# WeatherStation.net
KiCad netlist of a schematic drawn in EAGLE
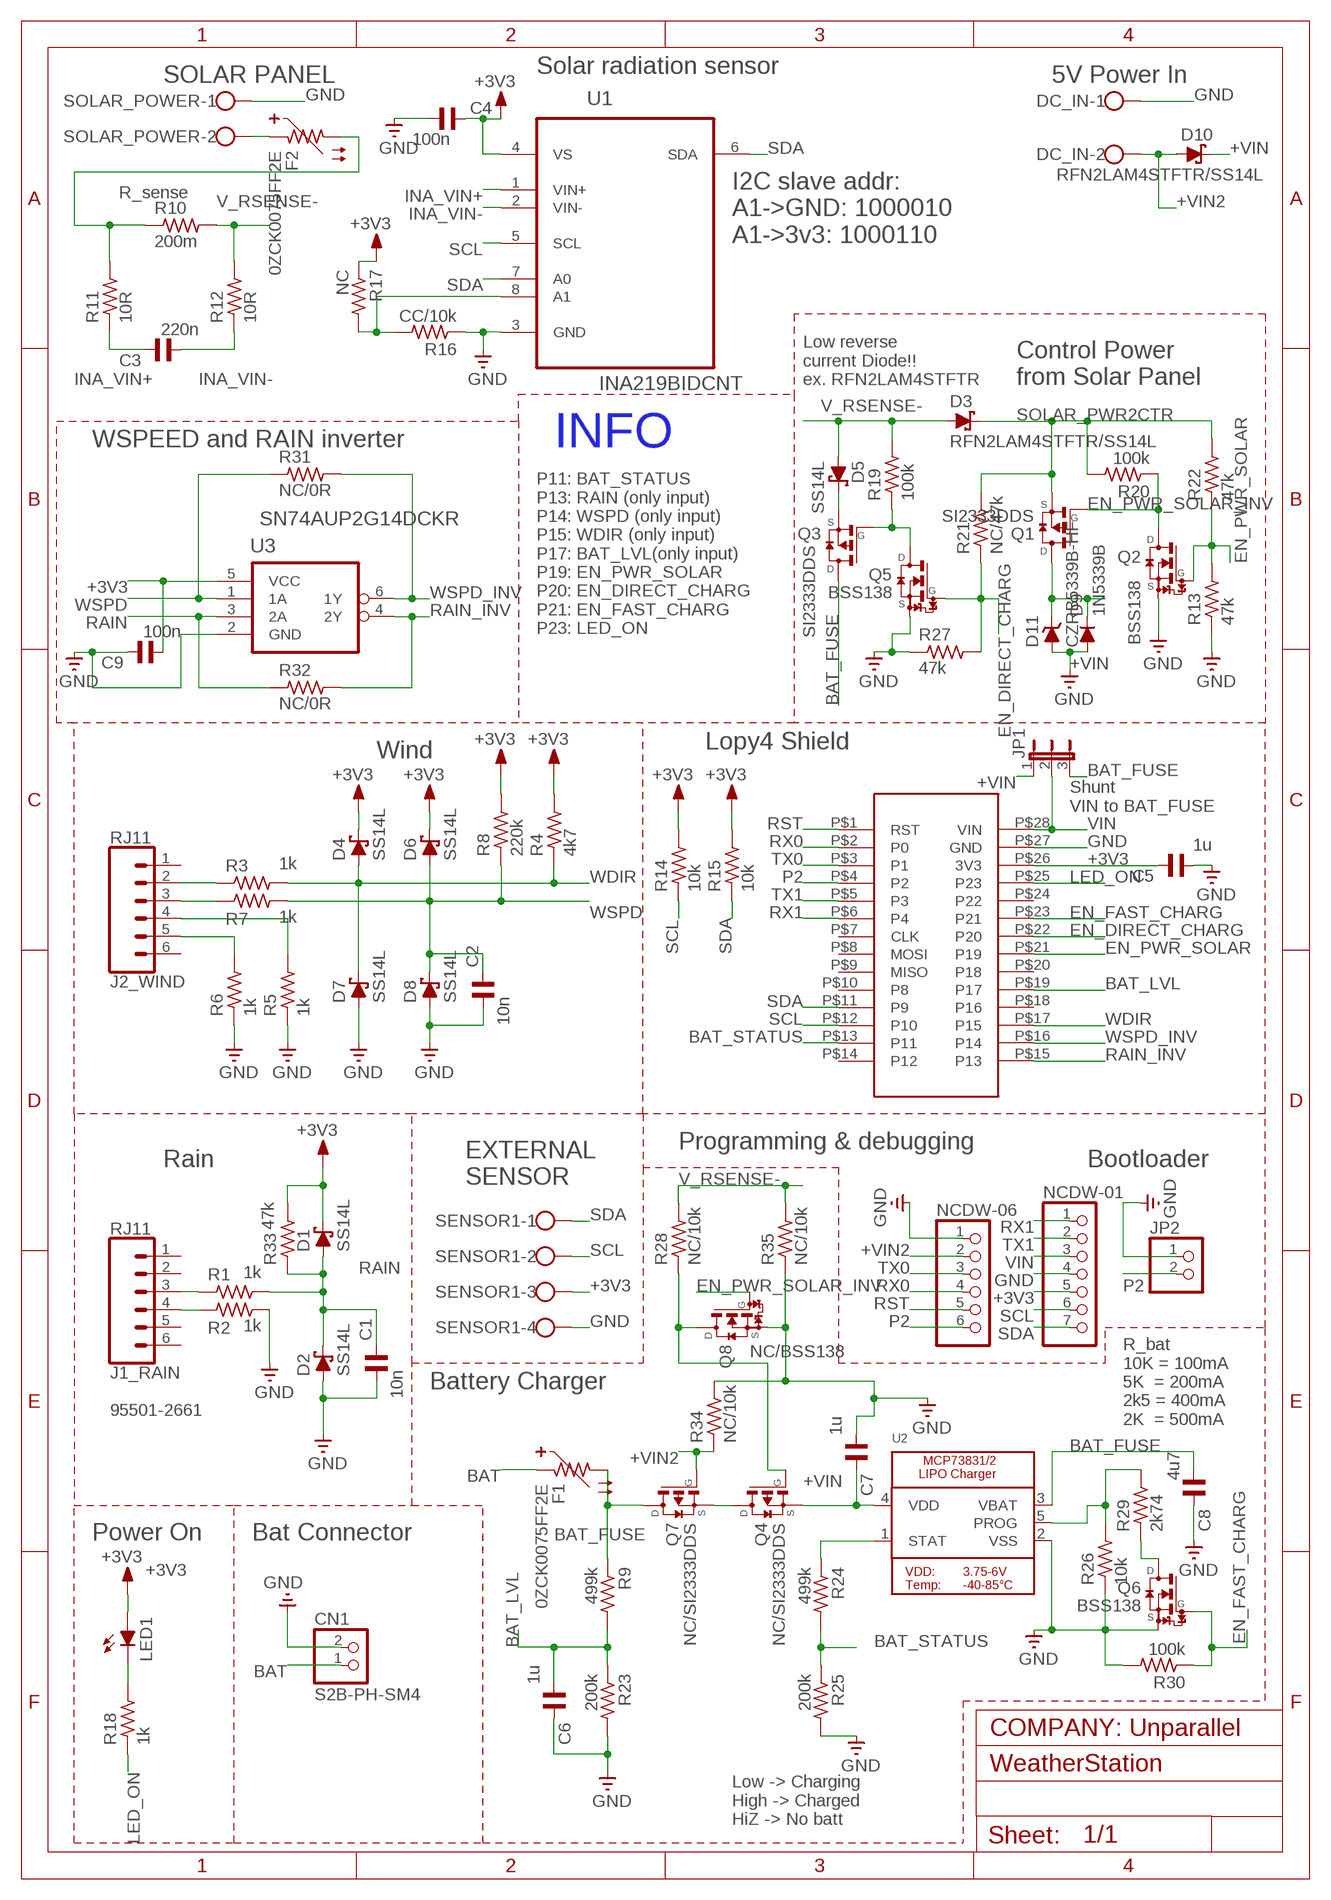
[diagram p0: schematic, sheet 1]

(export (version "E")
  (design (tool "Eeschema 10.0.6"))
  (components
    (comp (ref "C1")
      (value "10n")
      (footprint "eagle-import:C0603_C0805_PROTO_SLIM")
      (libsource (lib "eagle-import") (part "C-EUC0603/C0805_PROTO_SLIM"))
    )
    (comp (ref "C2")
      (value "10n")
      (footprint "eagle-import:C0603_C0805_PROTO_SLIM")
      (libsource (lib "eagle-import") (part "C-EUC0603/C0805_PROTO_SLIM"))
    )
    (comp (ref "C3")
      (value "220n")
      (footprint "eagle-import:C0603")
      (libsource (lib "eagle-import") (part "C-EUC0603"))
    )
    (comp (ref "C4")
      (value "100n")
      (footprint "eagle-import:C0603")
      (libsource (lib "eagle-import") (part "C-EUC0603"))
    )
    (comp (ref "C5")
      (value "1u")
      (footprint "eagle-import:C0603_C0805_PROTO_SLIM")
      (libsource (lib "eagle-import") (part "C-EUC0603/C0805_PROTO_SLIM"))
    )
    (comp (ref "C6")
      (value "1u")
      (footprint "eagle-import:C0603_C0805_PROTO_SLIM")
      (libsource (lib "eagle-import") (part "C-EUC0603/C0805_PROTO_SLIM"))
    )
    (comp (ref "C7")
      (value "1u")
      (footprint "eagle-import:C0603_C0805_PROTO_SLIM")
      (libsource (lib "eagle-import") (part "C-EUC0603/C0805_PROTO_SLIM"))
    )
    (comp (ref "C8")
      (value "4u7")
      (footprint "eagle-import:C0603_C0805_PROTO_SLIM")
      (libsource (lib "eagle-import") (part "C-EUC0603/C0805_PROTO_SLIM"))
    )
    (comp (ref "C9")
      (value "100n")
      (footprint "eagle-import:C0603")
      (libsource (lib "eagle-import") (part "C-EUC0603"))
    )
    (comp (ref "CN1")
      (value "S2B-PH-SM4")
      (footprint "eagle-import:JST-PH-2-SMT-RA")
      (libsource (lib "eagle-import") (part "JST_2PIN-SMT-RA"))
    )
    (comp (ref "D1")
      (value "SS14L")
      (footprint "eagle-import:SUB_SMA_PROTO")
      (libsource (lib "eagle-import") (part "SCHOTTKY-DIODESUB_SMA_PROTO"))
    )
    (comp (ref "D2")
      (value "SS14L")
      (footprint "eagle-import:SUB_SMA_PROTO")
      (libsource (lib "eagle-import") (part "SCHOTTKY-DIODESUB_SMA_PROTO"))
    )
    (comp (ref "D3")
      (value "RFN2LAM4STFTR/SS14L")
      (footprint "eagle-import:SMA_SOD-128_PROTO")
      (libsource (lib "eagle-import") (part "SCHOTTKY-DIODESMA_SOD-128_PROTO"))
    )
    (comp (ref "D4")
      (value "SS14L")
      (footprint "eagle-import:SUB_SMA_PROTO")
      (libsource (lib "eagle-import") (part "SCHOTTKY-DIODESUB_SMA_PROTO"))
    )
    (comp (ref "D5")
      (value "SS14L")
      (footprint "eagle-import:SUB_SMA_PROTO")
      (libsource (lib "eagle-import") (part "SCHOTTKY-DIODESUB_SMA_PROTO"))
    )
    (comp (ref "D6")
      (value "SS14L")
      (footprint "eagle-import:SUB_SMA_PROTO")
      (libsource (lib "eagle-import") (part "SCHOTTKY-DIODESUB_SMA_PROTO"))
    )
    (comp (ref "D7")
      (value "SS14L")
      (footprint "eagle-import:SUB_SMA_PROTO")
      (libsource (lib "eagle-import") (part "SCHOTTKY-DIODESUB_SMA_PROTO"))
    )
    (comp (ref "D8")
      (value "SS14L")
      (footprint "eagle-import:SUB_SMA_PROTO")
      (libsource (lib "eagle-import") (part "SCHOTTKY-DIODESUB_SMA_PROTO"))
    )
    (comp (ref "D9")
      (value "1N5339B")
      (footprint "eagle-import:DO15-12")
      (libsource (lib "eagle-import") (part "DIODE-DO15-12"))
    )
    (comp (ref "D10")
      (value "RFN2LAM4STFTR/SS14L")
      (footprint "eagle-import:SMA_SOD-128_PROTO")
      (libsource (lib "eagle-import") (part "SCHOTTKY-DIODESMA_SOD-128_PROTO"))
    )
    (comp (ref "D11")
      (value "CZRB5339B-HF")
      (footprint "eagle-import:SMB_PROTO")
      (libsource (lib "eagle-import") (part "ZENER-DIODE-PROTO"))
    )
    (comp (ref "DC_IN")
      (value "W237-102")
      (footprint "eagle-import:W237-102")
      (libsource (lib "eagle-import") (part "W237-102"))
    )
    (comp (ref "F1")
      (value "0ZCK0075FF2E")
      (footprint "eagle-import:R0603_R0805_PROTO_SLIM")
      (libsource (lib "eagle-import") (part "PTC-0603_0805_PROTO_SLIM"))
    )
    (comp (ref "F2")
      (value "0ZCK0075FF2E")
      (footprint "eagle-import:R0805")
      (libsource (lib "eagle-import") (part "PTC-0805"))
    )
    (comp (ref "J1_RAIN")
      (value "RJ11")
      (footprint "eagle-import:RJ11-6")
      (libsource (lib "eagle-import") (part "RJ11-6"))
    )
    (comp (ref "J2_WIND")
      (value "RJ11")
      (footprint "eagle-import:RJ11-6")
      (libsource (lib "eagle-import") (part "RJ11-6"))
    )
    (comp (ref "JP1")
      (value "JP2E-0805")
      (footprint "eagle-import:R0805_2")
      (libsource (lib "eagle-import") (part "JP2E-0805"))
    )
    (comp (ref "JP2")
      (value "PINHD-1X2")
      (footprint "eagle-import:1X02")
      (libsource (lib "eagle-import") (part "PINHD-1X2"))
    )
    (comp (ref "LED1")
      (value "LEDCHIP-LED0805")
      (footprint "eagle-import:CHIP-LED0805")
      (libsource (lib "eagle-import") (part "LEDCHIP-LED0805"))
    )
    (comp (ref "NCDW-01")
      (value "PINHD-1X7")
      (footprint "eagle-import:1X07")
      (libsource (lib "eagle-import") (part "PINHD-1X7"))
    )
    (comp (ref "NCDW-06")
      (value "PINHD-1X6")
      (footprint "eagle-import:1X06")
      (libsource (lib "eagle-import") (part "PINHD-1X6"))
    )
    (comp (ref "Q1")
      (value "SI2333DDS")
      (footprint "eagle-import:SOT23_PROTO_SLIM")
      (libsource (lib "eagle-import") (part "SI2333DDSPROTO_SLIM"))
    )
    (comp (ref "Q2")
      (value "BSS138")
      (footprint "eagle-import:SOT23_PROTO_SLIM")
      (libsource (lib "eagle-import") (part "NX7002AKPROTO_SLIM"))
    )
    (comp (ref "Q3")
      (value "SI2333DDS")
      (footprint "eagle-import:SOT23_PROTO_SLIM")
      (libsource (lib "eagle-import") (part "SI2333DDSPROTO_SLIM"))
    )
    (comp (ref "Q4")
      (value "NC/SI2333DDS")
      (footprint "eagle-import:SOT23_PROTO_SLIM")
      (libsource (lib "eagle-import") (part "SI2333DDSPROTO_SLIM"))
    )
    (comp (ref "Q5")
      (value "BSS138")
      (footprint "eagle-import:SOT23_PROTO_SLIM")
      (libsource (lib "eagle-import") (part "NX7002AKPROTO_SLIM"))
    )
    (comp (ref "Q6")
      (value "BSS138")
      (footprint "eagle-import:SOT23_PROTO_SLIM")
      (libsource (lib "eagle-import") (part "NX7002AKPROTO_SLIM"))
    )
    (comp (ref "Q7")
      (value "NC/SI2333DDS")
      (footprint "eagle-import:SOT23_PROTO_SLIM")
      (libsource (lib "eagle-import") (part "SI2333DDSPROTO_SLIM"))
    )
    (comp (ref "Q8")
      (value "NC/BSS138")
      (footprint "eagle-import:SOT23_PROTO_SLIM")
      (libsource (lib "eagle-import") (part "NX7002AKPROTO_SLIM"))
    )
    (comp (ref "R1")
      (value "1k")
      (footprint "eagle-import:R0603")
      (libsource (lib "eagle-import") (part "R-EU_R0603"))
    )
    (comp (ref "R2")
      (value "1k")
      (footprint "eagle-import:R0603")
      (libsource (lib "eagle-import") (part "R-EU_R0603"))
    )
    (comp (ref "R3")
      (value "1k")
      (footprint "eagle-import:R0603")
      (libsource (lib "eagle-import") (part "R-EU_R0603"))
    )
    (comp (ref "R4")
      (value "4k7")
      (footprint "eagle-import:R0603_R0805_PROTO_SLIM")
      (libsource (lib "eagle-import") (part "R-EU_R0603/R0805_PROTO_SLIM"))
    )
    (comp (ref "R5")
      (value "1k")
      (footprint "eagle-import:R0603")
      (libsource (lib "eagle-import") (part "R-EU_R0603"))
    )
    (comp (ref "R6")
      (value "1k")
      (footprint "eagle-import:R0603")
      (libsource (lib "eagle-import") (part "R-EU_R0603"))
    )
    (comp (ref "R7")
      (value "1k")
      (footprint "eagle-import:R0603")
      (libsource (lib "eagle-import") (part "R-EU_R0603"))
    )
    (comp (ref "R8")
      (value "220k")
      (footprint "eagle-import:R0603_R0805_PROTO_SLIM")
      (libsource (lib "eagle-import") (part "R-EU_R0603/R0805_PROTO_SLIM"))
    )
    (comp (ref "R9")
      (value "499k")
      (footprint "eagle-import:R0603_R0805_PROTO_SLIM")
      (libsource (lib "eagle-import") (part "R-EU_R0603/R0805_PROTO_SLIM"))
    )
    (comp (ref "R10")
      (value "200m")
      (footprint "eagle-import:R0603_R0805_PROTO_SLIM")
      (libsource (lib "eagle-import") (part "R-EU_R0603/R0805_PROTO_SLIM"))
    )
    (comp (ref "R11")
      (value "10R")
      (footprint "eagle-import:R0603")
      (libsource (lib "eagle-import") (part "R-EU_R0603"))
    )
    (comp (ref "R12")
      (value "10R")
      (footprint "eagle-import:R0603")
      (libsource (lib "eagle-import") (part "R-EU_R0603"))
    )
    (comp (ref "R13")
      (value "47k")
      (footprint "eagle-import:R0603")
      (libsource (lib "eagle-import") (part "R-EU_R0603"))
    )
    (comp (ref "R14")
      (value "10k")
      (footprint "eagle-import:R0603")
      (libsource (lib "eagle-import") (part "R-EU_R0603"))
    )
    (comp (ref "R15")
      (value "10k")
      (footprint "eagle-import:R0603")
      (libsource (lib "eagle-import") (part "R-EU_R0603"))
    )
    (comp (ref "R16")
      (value "CC/10k")
      (footprint "eagle-import:R0603")
      (libsource (lib "eagle-import") (part "R-EU_R0603"))
    )
    (comp (ref "R17")
      (value "NC")
      (footprint "eagle-import:R0603")
      (libsource (lib "eagle-import") (part "R-EU_R0603"))
    )
    (comp (ref "R18")
      (value "1k")
      (footprint "eagle-import:R0603")
      (libsource (lib "eagle-import") (part "R-EU_R0603"))
    )
    (comp (ref "R19")
      (value "100k")
      (footprint "eagle-import:R0603")
      (libsource (lib "eagle-import") (part "R-EU_R0603"))
    )
    (comp (ref "R20")
      (value "100k")
      (footprint "eagle-import:R0603")
      (libsource (lib "eagle-import") (part "R-EU_R0603"))
    )
    (comp (ref "R21")
      (value "NC/47k")
      (footprint "eagle-import:R0603")
      (libsource (lib "eagle-import") (part "R-EU_R0603"))
    )
    (comp (ref "R22")
      (value "47k")
      (footprint "eagle-import:R0603")
      (libsource (lib "eagle-import") (part "R-EU_R0603"))
    )
    (comp (ref "R23")
      (value "200k")
      (footprint "eagle-import:R0603_R0805_PROTO_SLIM")
      (libsource (lib "eagle-import") (part "R-EU_R0603/R0805_PROTO_SLIM"))
    )
    (comp (ref "R24")
      (value "499k")
      (footprint "eagle-import:R0603_R0805_PROTO_SLIM")
      (libsource (lib "eagle-import") (part "R-EU_R0603/R0805_PROTO_SLIM"))
    )
    (comp (ref "R25")
      (value "200k")
      (footprint "eagle-import:R0603_R0805_PROTO_SLIM")
      (libsource (lib "eagle-import") (part "R-EU_R0603/R0805_PROTO_SLIM"))
    )
    (comp (ref "R26")
      (value "10k")
      (footprint "eagle-import:R0603_R0805_PROTO_SLIM")
      (libsource (lib "eagle-import") (part "R-EU_R0603/R0805_PROTO_SLIM"))
    )
    (comp (ref "R27")
      (value "47k")
      (footprint "eagle-import:R0603")
      (libsource (lib "eagle-import") (part "R-EU_R0603"))
    )
    (comp (ref "R28")
      (value "NC/10k")
      (footprint "eagle-import:R0603")
      (libsource (lib "eagle-import") (part "R-EU_R0603"))
    )
    (comp (ref "R29")
      (value "2k74")
      (footprint "eagle-import:R0603_R0805_PROTO_SLIM")
      (libsource (lib "eagle-import") (part "R-EU_R0603/R0805_PROTO_SLIM"))
    )
    (comp (ref "R30")
      (value "100k")
      (footprint "eagle-import:R0603_R0805_PROTO_SLIM")
      (libsource (lib "eagle-import") (part "R-EU_R0603/R0805_PROTO_SLIM"))
    )
    (comp (ref "R31")
      (value "NC/0R")
      (footprint "eagle-import:R0603_R0805_PROTO_SLIM")
      (libsource (lib "eagle-import") (part "R-EU_R0603/R0805_PROTO_SLIM"))
    )
    (comp (ref "R32")
      (value "NC/0R")
      (footprint "eagle-import:R0603_R0805_PROTO_SLIM")
      (libsource (lib "eagle-import") (part "R-EU_R0603/R0805_PROTO_SLIM"))
    )
    (comp (ref "R33")
      (value "47k")
      (footprint "eagle-import:R0603")
      (libsource (lib "eagle-import") (part "R-EU_R0603"))
    )
    (comp (ref "R34")
      (value "NC/10k")
      (footprint "eagle-import:R0603")
      (libsource (lib "eagle-import") (part "R-EU_R0603"))
    )
    (comp (ref "R35")
      (value "NC/10k")
      (footprint "eagle-import:R0603")
      (libsource (lib "eagle-import") (part "R-EU_R0603"))
    )
    (comp (ref "SENSOR1")
      (value "W237-4")
      (footprint "eagle-import:W237-4")
      (libsource (lib "eagle-import") (part "W237-4"))
    )
    (comp (ref "SOLAR_POWER")
      (value "W237-102")
      (footprint "eagle-import:W237-102")
      (libsource (lib "eagle-import") (part "W237-102"))
    )
    (comp (ref "U$2")
      (value "LOPY4_SHIELD")
      (footprint "eagle-import:LOPY4_SHIELD")
      (libsource (lib "eagle-import") (part "LOPY4_SHIELD"))
    )
    (comp (ref "U1")
      (value "INA219BIDCNT")
      (footprint "eagle-import:SOT65P280X145-8N")
      (libsource (lib "eagle-import") (part "INA219BIDCNT"))
    )
    (comp (ref "U2")
      (value "MCP73831/2")
      (footprint "eagle-import:SOT23-5")
      (libsource (lib "eagle-import") (part "MCP73831/2"))
    )
    (comp (ref "U3")
      (value "SN74AUP2G14DCKR")
      (footprint "eagle-import:SOT65P210X110-6N_EDIT")
      (libsource (lib "eagle-import") (part "SN74AUP2G14-DCKR"))
    )
  )
  (nets
    (net (code "1") (name "+3V3") (class "Default")
      (node (ref "C4") (pin "1") (pinfunction "1_1") (pintype "passive"))
      (node (ref "C5") (pin "1") (pinfunction "1_1") (pintype "passive"))
      (node (ref "C9") (pin "2") (pinfunction "2_2") (pintype "passive"))
      (node (ref "D1") (pin "C") (pinfunction "C_C") (pintype "passive"))
      (node (ref "D4") (pin "C") (pinfunction "C_C") (pintype "passive"))
      (node (ref "D6") (pin "C") (pinfunction "C_C") (pintype "passive"))
      (node (ref "LED1") (pin "A") (pinfunction "A_A") (pintype "passive"))
      (node (ref "NCDW-01") (pin "5") (pinfunction "5_5") (pintype "passive"))
      (node (ref "R14") (pin "2") (pinfunction "2_2") (pintype "passive"))
      (node (ref "R15") (pin "2") (pinfunction "2_2") (pintype "passive"))
      (node (ref "R17") (pin "1") (pinfunction "1_1") (pintype "passive"))
      (node (ref "R33") (pin "2") (pinfunction "2_2") (pintype "passive"))
      (node (ref "R4") (pin "2") (pinfunction "2_2") (pintype "passive"))
      (node (ref "R8") (pin "2") (pinfunction "2_2") (pintype "passive"))
      (node (ref "SENSOR1") (pin "3") (pinfunction "KL_3") (pintype "passive"))
      (node (ref "U$2") (pin "P$26") (pinfunction "3V3_P$26") (pintype "power_in"))
      (node (ref "U1") (pin "4") (pinfunction "VS_4") (pintype "power_in"))
      (node (ref "U3") (pin "5") (pinfunction "VCC_5") (pintype "power_in"))
    )
    (net (code "2") (name "/+VIN") (class "Default")
      (node (ref "C7") (pin "1") (pinfunction "1_1") (pintype "passive"))
      (node (ref "D10") (pin "C") (pinfunction "C_C") (pintype "passive"))
      (node (ref "D11") (pin "C") (pinfunction "C_C") (pintype "passive"))
      (node (ref "D9") (pin "C") (pinfunction "C_C") (pintype "passive"))
      (node (ref "JP1") (pin "1") (pinfunction "1_1") (pintype "passive"))
      (node (ref "Q1") (pin "3") (pinfunction "D_3") (pintype "passive"))
      (node (ref "Q4") (pin "2") (pinfunction "S_2") (pintype "passive"))
      (node (ref "U2") (pin "4") (pinfunction "VDD_4") (pintype "power_in"))
    )
    (net (code "3") (name "/+VIN2") (class "Default")
      (node (ref "D10") (pin "A") (pinfunction "A_A") (pintype "passive"))
      (node (ref "DC_IN") (pin "2") (pinfunction "KL_2") (pintype "passive"))
      (node (ref "NCDW-06") (pin "2") (pinfunction "2_2") (pintype "passive"))
      (node (ref "Q7") (pin "1") (pinfunction "G_1") (pintype "passive"))
      (node (ref "R34") (pin "1") (pinfunction "1_1") (pintype "passive"))
    )
    (net (code "4") (name "/BAT") (class "Default")
      (node (ref "CN1") (pin "1") (pinfunction "2_1") (pintype "passive"))
      (node (ref "F1") (pin "1") (pinfunction "1_1") (pintype "passive"))
    )
    (net (code "5") (name "/BAT_FUSE") (class "Default")
      (node (ref "C8") (pin "2") (pinfunction "2_2") (pintype "passive"))
      (node (ref "F1") (pin "2") (pinfunction "2_2") (pintype "passive"))
      (node (ref "JP1") (pin "3") (pinfunction "3_3") (pintype "passive"))
      (node (ref "Q3") (pin "3") (pinfunction "D_3") (pintype "passive"))
      (node (ref "Q7") (pin "3") (pinfunction "D_3") (pintype "passive"))
      (node (ref "R9") (pin "1") (pinfunction "1_1") (pintype "passive"))
      (node (ref "U2") (pin "3") (pinfunction "VBAT_3") (pintype "power_in"))
    )
    (net (code "6") (name "/BAT_LVL") (class "Default")
      (node (ref "C6") (pin "2") (pinfunction "2_2") (pintype "passive"))
      (node (ref "R23") (pin "1") (pinfunction "1_1") (pintype "passive"))
      (node (ref "R9") (pin "2") (pinfunction "2_2") (pintype "passive"))
      (node (ref "U$2") (pin "P$19") (pinfunction "P17_P$19") (pintype "bidirectional"))
    )
    (net (code "7") (name "/BAT_STATUS") (class "Default")
      (node (ref "R24") (pin "2") (pinfunction "2_2") (pintype "passive"))
      (node (ref "R25") (pin "1") (pinfunction "1_1") (pintype "passive"))
      (node (ref "U$2") (pin "P$13") (pinfunction "P11_P$13") (pintype "bidirectional"))
    )
    (net (code "8") (name "/EN_DIRECT_CHARG") (class "Default")
      (node (ref "Q5") (pin "1") (pinfunction "G_1") (pintype "passive"))
      (node (ref "R21") (pin "1") (pinfunction "1_1") (pintype "passive"))
      (node (ref "R27") (pin "2") (pinfunction "2_2") (pintype "passive"))
      (node (ref "U$2") (pin "P$22") (pinfunction "P20_P$22") (pintype "bidirectional"))
    )
    (net (code "9") (name "/EN_FAST_CHARG") (class "Default")
      (node (ref "Q6") (pin "1") (pinfunction "G_1") (pintype "passive"))
      (node (ref "R30") (pin "1") (pinfunction "1_1") (pintype "passive"))
      (node (ref "U$2") (pin "P$23") (pinfunction "P21_P$23") (pintype "bidirectional"))
    )
    (net (code "10") (name "/EN_PWR_SOLAR") (class "Default")
      (node (ref "Q2") (pin "1") (pinfunction "G_1") (pintype "passive"))
      (node (ref "R13") (pin "2") (pinfunction "2_2") (pintype "passive"))
      (node (ref "R22") (pin "1") (pinfunction "1_1") (pintype "passive"))
      (node (ref "U$2") (pin "P$21") (pinfunction "P19_P$21") (pintype "bidirectional"))
    )
    (net (code "11") (name "/EN_PWR_SOLAR_INV") (class "Default")
      (node (ref "Q1") (pin "1") (pinfunction "G_1") (pintype "passive"))
      (node (ref "Q2") (pin "3") (pinfunction "D_3") (pintype "passive"))
      (node (ref "Q8") (pin "1") (pinfunction "G_1") (pintype "passive"))
      (node (ref "R20") (pin "1") (pinfunction "1_1") (pintype "passive"))
    )
    (net (code "12") (name "/INA_VIN+") (class "Default")
      (node (ref "C3") (pin "1") (pinfunction "1_1") (pintype "passive"))
      (node (ref "R11") (pin "1") (pinfunction "1_1") (pintype "passive"))
      (node (ref "U1") (pin "1") (pinfunction "VIN+_1") (pintype "power_in"))
    )
    (net (code "13") (name "/INA_VIN-") (class "Default")
      (node (ref "C3") (pin "2") (pinfunction "2_2") (pintype "passive"))
      (node (ref "R12") (pin "1") (pinfunction "1_1") (pintype "passive"))
      (node (ref "U1") (pin "2") (pinfunction "VIN-_2") (pintype "power_in"))
    )
    (net (code "14") (name "/LED_ON") (class "Default")
      (node (ref "R18") (pin "1") (pinfunction "1_1") (pintype "passive"))
      (node (ref "U$2") (pin "P$25") (pinfunction "P23_P$25") (pintype "bidirectional"))
    )
    (net (code "15") (name "/P2") (class "Default")
      (node (ref "JP2") (pin "2") (pinfunction "2_2") (pintype "passive"))
      (node (ref "NCDW-06") (pin "6") (pinfunction "6_6") (pintype "passive"))
      (node (ref "U$2") (pin "P$4") (pinfunction "P2_P$4") (pintype "bidirectional"))
    )
    (net (code "16") (name "/RAIN") (class "Default")
      (node (ref "C1") (pin "1") (pinfunction "1_1") (pintype "passive"))
      (node (ref "D1") (pin "A") (pinfunction "A_A") (pintype "passive"))
      (node (ref "D2") (pin "C") (pinfunction "C_C") (pintype "passive"))
      (node (ref "R1") (pin "2") (pinfunction "2_2") (pintype "passive"))
      (node (ref "R32") (pin "1") (pinfunction "1_1") (pintype "passive"))
      (node (ref "R33") (pin "1") (pinfunction "1_1") (pintype "passive"))
      (node (ref "U3") (pin "3") (pinfunction "2A_3") (pintype "input"))
    )
    (net (code "17") (name "/RAIN_INV") (class "Default")
      (node (ref "R32") (pin "2") (pinfunction "2_2") (pintype "passive"))
      (node (ref "U$2") (pin "P$15") (pinfunction "P13_P$15") (pintype "bidirectional"))
      (node (ref "U3") (pin "4") (pinfunction "2Y_4") (pintype "output"))
    )
    (net (code "18") (name "/RST") (class "Default")
      (node (ref "NCDW-06") (pin "5") (pinfunction "5_5") (pintype "passive"))
      (node (ref "U$2") (pin "P$1") (pinfunction "RST_P$1") (pintype "input"))
    )
    (net (code "19") (name "/RX0") (class "Default")
      (node (ref "NCDW-06") (pin "4") (pinfunction "4_4") (pintype "passive"))
      (node (ref "U$2") (pin "P$2") (pinfunction "P0_P$2") (pintype "bidirectional"))
    )
    (net (code "20") (name "/RX1") (class "Default")
      (node (ref "NCDW-01") (pin "1") (pinfunction "1_1") (pintype "passive"))
      (node (ref "U$2") (pin "P$6") (pinfunction "P4_P$6") (pintype "bidirectional"))
    )
    (net (code "21") (name "/SCL") (class "Default")
      (node (ref "NCDW-01") (pin "6") (pinfunction "6_6") (pintype "passive"))
      (node (ref "R14") (pin "1") (pinfunction "1_1") (pintype "passive"))
      (node (ref "SENSOR1") (pin "2") (pinfunction "KL_2") (pintype "passive"))
      (node (ref "U$2") (pin "P$12") (pinfunction "P10_P$12") (pintype "bidirectional"))
      (node (ref "U1") (pin "5") (pinfunction "SCL_5") (pintype "input"))
    )
    (net (code "22") (name "/SDA") (class "Default")
      (node (ref "NCDW-01") (pin "7") (pinfunction "7_7") (pintype "passive"))
      (node (ref "R15") (pin "1") (pinfunction "1_1") (pintype "passive"))
      (node (ref "SENSOR1") (pin "1") (pinfunction "KL_1") (pintype "passive"))
      (node (ref "U$2") (pin "P$11") (pinfunction "P9_P$11") (pintype "bidirectional"))
      (node (ref "U1") (pin "6") (pinfunction "SDA_6") (pintype "bidirectional"))
      (node (ref "U1") (pin "7") (pinfunction "A0_7") (pintype "input"))
    )
    (net (code "23") (name "/SOLAR_PWR2CTR") (class "Default")
      (node (ref "D3") (pin "C") (pinfunction "C_C") (pintype "passive"))
      (node (ref "Q1") (pin "2") (pinfunction "S_2") (pintype "passive"))
      (node (ref "R20") (pin "2") (pinfunction "2_2") (pintype "passive"))
      (node (ref "R21") (pin "2") (pinfunction "2_2") (pintype "passive"))
      (node (ref "R22") (pin "2") (pinfunction "2_2") (pintype "passive"))
    )
    (net (code "24") (name "/TX0") (class "Default")
      (node (ref "NCDW-06") (pin "3") (pinfunction "3_3") (pintype "passive"))
      (node (ref "U$2") (pin "P$3") (pinfunction "P1_P$3") (pintype "bidirectional"))
    )
    (net (code "25") (name "/TX1") (class "Default")
      (node (ref "NCDW-01") (pin "2") (pinfunction "2_2") (pintype "passive"))
      (node (ref "U$2") (pin "P$5") (pinfunction "P3_P$5") (pintype "bidirectional"))
    )
    (net (code "26") (name "/VIN") (class "Default")
      (node (ref "JP1") (pin "2") (pinfunction "2_2") (pintype "passive"))
      (node (ref "NCDW-01") (pin "3") (pinfunction "3_3") (pintype "passive"))
      (node (ref "U$2") (pin "P$28") (pinfunction "VIN_P$28") (pintype "power_in"))
    )
    (net (code "27") (name "/V_RSENSE-") (class "Default")
      (node (ref "D3") (pin "A") (pinfunction "A_A") (pintype "passive"))
      (node (ref "D5") (pin "A") (pinfunction "A_A") (pintype "passive"))
      (node (ref "R10") (pin "2") (pinfunction "2_2") (pintype "passive"))
      (node (ref "R12") (pin "2") (pinfunction "2_2") (pintype "passive"))
      (node (ref "R19") (pin "2") (pinfunction "2_2") (pintype "passive"))
      (node (ref "R28") (pin "2") (pinfunction "2_2") (pintype "passive"))
      (node (ref "R35") (pin "2") (pinfunction "2_2") (pintype "passive"))
    )
    (net (code "28") (name "/WDIR") (class "Default")
      (node (ref "D4") (pin "A") (pinfunction "A_A") (pintype "passive"))
      (node (ref "D7") (pin "C") (pinfunction "C_C") (pintype "passive"))
      (node (ref "R3") (pin "2") (pinfunction "2_2") (pintype "passive"))
      (node (ref "R4") (pin "1") (pinfunction "1_1") (pintype "passive"))
      (node (ref "U$2") (pin "P$17") (pinfunction "P15_P$17") (pintype "bidirectional"))
    )
    (net (code "29") (name "/WSPD") (class "Default")
      (node (ref "C2") (pin "1") (pinfunction "1_1") (pintype "passive"))
      (node (ref "D6") (pin "A") (pinfunction "A_A") (pintype "passive"))
      (node (ref "D8") (pin "C") (pinfunction "C_C") (pintype "passive"))
      (node (ref "R31") (pin "1") (pinfunction "1_1") (pintype "passive"))
      (node (ref "R7") (pin "2") (pinfunction "2_2") (pintype "passive"))
      (node (ref "R8") (pin "1") (pinfunction "1_1") (pintype "passive"))
      (node (ref "U3") (pin "1") (pinfunction "1A_1") (pintype "input"))
    )
    (net (code "30") (name "/WSPD_INV") (class "Default")
      (node (ref "R31") (pin "2") (pinfunction "2_2") (pintype "passive"))
      (node (ref "U$2") (pin "P$16") (pinfunction "P14_P$16") (pintype "bidirectional"))
      (node (ref "U3") (pin "6") (pinfunction "1Y_6") (pintype "output"))
    )
    (net (code "31") (name "GND") (class "Default")
      (node (ref "C1") (pin "2") (pinfunction "2_2") (pintype "passive"))
      (node (ref "C2") (pin "2") (pinfunction "2_2") (pintype "passive"))
      (node (ref "C4") (pin "2") (pinfunction "2_2") (pintype "passive"))
      (node (ref "C5") (pin "2") (pinfunction "2_2") (pintype "passive"))
      (node (ref "C6") (pin "1") (pinfunction "1_1") (pintype "passive"))
      (node (ref "C7") (pin "2") (pinfunction "2_2") (pintype "passive"))
      (node (ref "C8") (pin "1") (pinfunction "1_1") (pintype "passive"))
      (node (ref "C9") (pin "1") (pinfunction "1_1") (pintype "passive"))
      (node (ref "CN1") (pin "2") (pinfunction "1_2") (pintype "passive"))
      (node (ref "D11") (pin "A") (pinfunction "A_A") (pintype "passive"))
      (node (ref "D2") (pin "A") (pinfunction "A_A") (pintype "passive"))
      (node (ref "D7") (pin "A") (pinfunction "A_A") (pintype "passive"))
      (node (ref "D8") (pin "A") (pinfunction "A_A") (pintype "passive"))
      (node (ref "D9") (pin "A") (pinfunction "A_A") (pintype "passive"))
      (node (ref "DC_IN") (pin "1") (pinfunction "KL_1") (pintype "passive"))
      (node (ref "JP2") (pin "1") (pinfunction "1_1") (pintype "passive"))
      (node (ref "NCDW-01") (pin "4") (pinfunction "4_4") (pintype "passive"))
      (node (ref "NCDW-06") (pin "1") (pinfunction "1_1") (pintype "passive"))
      (node (ref "Q2") (pin "2") (pinfunction "S_2") (pintype "passive"))
      (node (ref "Q5") (pin "2") (pinfunction "S_2") (pintype "passive"))
      (node (ref "Q6") (pin "2") (pinfunction "S_2") (pintype "passive"))
      (node (ref "Q8") (pin "2") (pinfunction "S_2") (pintype "passive"))
      (node (ref "R13") (pin "1") (pinfunction "1_1") (pintype "passive"))
      (node (ref "R16") (pin "1") (pinfunction "1_1") (pintype "passive"))
      (node (ref "R2") (pin "2") (pinfunction "2_2") (pintype "passive"))
      (node (ref "R23") (pin "2") (pinfunction "2_2") (pintype "passive"))
      (node (ref "R25") (pin "2") (pinfunction "2_2") (pintype "passive"))
      (node (ref "R26") (pin "1") (pinfunction "1_1") (pintype "passive"))
      (node (ref "R27") (pin "1") (pinfunction "1_1") (pintype "passive"))
      (node (ref "R30") (pin "2") (pinfunction "2_2") (pintype "passive"))
      (node (ref "R34") (pin "2") (pinfunction "2_2") (pintype "passive"))
      (node (ref "R35") (pin "1") (pinfunction "1_1") (pintype "passive"))
      (node (ref "R5") (pin "1") (pinfunction "1_1") (pintype "passive"))
      (node (ref "R6") (pin "1") (pinfunction "1_1") (pintype "passive"))
      (node (ref "SENSOR1") (pin "4") (pinfunction "KL_4") (pintype "passive"))
      (node (ref "SOLAR_POWER") (pin "1") (pinfunction "KL_1") (pintype "passive"))
      (node (ref "U$2") (pin "P$27") (pinfunction "GND_P$27") (pintype "power_in"))
      (node (ref "U1") (pin "3") (pinfunction "GND_3") (pintype "passive"))
      (node (ref "U2") (pin "2") (pinfunction "VSS_2") (pintype "power_in"))
      (node (ref "U3") (pin "2") (pinfunction "GND_2") (pintype "passive"))
    )
    (net (code "32") (name "Net-(F2-Pad2)") (class "Default")
      (node (ref "F2") (pin "2") (pinfunction "2_2") (pintype "passive"))
      (node (ref "R10") (pin "1") (pinfunction "1_1") (pintype "passive"))
      (node (ref "R11") (pin "2") (pinfunction "2_2") (pintype "passive"))
    )
    (net (code "33") (name "Net-(J1_RAIN-Pad3)") (class "Default")
      (node (ref "J1_RAIN") (pin "3") (pinfunction "3_3") (pintype "passive"))
      (node (ref "R1") (pin "1") (pinfunction "1_1") (pintype "passive"))
    )
    (net (code "34") (name "Net-(J1_RAIN-Pad4)") (class "Default")
      (node (ref "J1_RAIN") (pin "4") (pinfunction "4_4") (pintype "passive"))
      (node (ref "R2") (pin "1") (pinfunction "1_1") (pintype "passive"))
    )
    (net (code "35") (name "Net-(J2_WIND-Pad2)") (class "Default")
      (node (ref "J2_WIND") (pin "2") (pinfunction "2_2") (pintype "passive"))
      (node (ref "R3") (pin "1") (pinfunction "1_1") (pintype "passive"))
    )
    (net (code "36") (name "Net-(J2_WIND-Pad3)") (class "Default")
      (node (ref "J2_WIND") (pin "3") (pinfunction "3_3") (pintype "passive"))
      (node (ref "R7") (pin "1") (pinfunction "1_1") (pintype "passive"))
    )
    (net (code "37") (name "Net-(J2_WIND-Pad4)") (class "Default")
      (node (ref "J2_WIND") (pin "4") (pinfunction "4_4") (pintype "passive"))
      (node (ref "R5") (pin "2") (pinfunction "2_2") (pintype "passive"))
    )
    (net (code "38") (name "Net-(J2_WIND-Pad5)") (class "Default")
      (node (ref "J2_WIND") (pin "5") (pinfunction "5_5") (pintype "passive"))
      (node (ref "R6") (pin "2") (pinfunction "2_2") (pintype "passive"))
    )
    (net (code "39") (name "Net-(LED1-PadC)") (class "Default")
      (node (ref "LED1") (pin "C") (pinfunction "C_C") (pintype "passive"))
      (node (ref "R18") (pin "2") (pinfunction "2_2") (pintype "passive"))
    )
    (net (code "40") (name "Net-(Q3-G)") (class "Default")
      (node (ref "Q3") (pin "1") (pinfunction "G_1") (pintype "passive"))
      (node (ref "Q5") (pin "3") (pinfunction "D_3") (pintype "passive"))
      (node (ref "R19") (pin "1") (pinfunction "1_1") (pintype "passive"))
    )
    (net (code "41") (name "Net-(Q3-S)") (class "Default")
      (node (ref "D5") (pin "C") (pinfunction "C_C") (pintype "passive"))
      (node (ref "Q3") (pin "2") (pinfunction "S_2") (pintype "passive"))
    )
    (net (code "42") (name "Net-(Q4-D)") (class "Default")
      (node (ref "Q4") (pin "3") (pinfunction "D_3") (pintype "passive"))
      (node (ref "Q7") (pin "2") (pinfunction "S_2") (pintype "passive"))
    )
    (net (code "43") (name "Net-(Q4-G)") (class "Default")
      (node (ref "Q4") (pin "1") (pinfunction "G_1") (pintype "passive"))
      (node (ref "Q8") (pin "3") (pinfunction "D_3") (pintype "passive"))
      (node (ref "R28") (pin "1") (pinfunction "1_1") (pintype "passive"))
    )
    (net (code "44") (name "Net-(Q6-D)") (class "Default")
      (node (ref "Q6") (pin "3") (pinfunction "D_3") (pintype "passive"))
      (node (ref "R29") (pin "1") (pinfunction "1_1") (pintype "passive"))
    )
    (net (code "45") (name "Net-(SOLAR_POWERB-KL)") (class "Default")
      (node (ref "F2") (pin "1") (pinfunction "1_1") (pintype "passive"))
      (node (ref "SOLAR_POWER") (pin "2") (pinfunction "KL_2") (pintype "passive"))
    )
    (net (code "46") (name "Net-(U1-A1)") (class "Default")
      (node (ref "R16") (pin "2") (pinfunction "2_2") (pintype "passive"))
      (node (ref "R17") (pin "2") (pinfunction "2_2") (pintype "passive"))
      (node (ref "U1") (pin "8") (pinfunction "A1_8") (pintype "input"))
    )
    (net (code "47") (name "Net-(U2-PROG)") (class "Default")
      (node (ref "R26") (pin "2") (pinfunction "2_2") (pintype "passive"))
      (node (ref "R29") (pin "2") (pinfunction "2_2") (pintype "passive"))
      (node (ref "U2") (pin "5") (pinfunction "PROG_5") (pintype "input"))
    )
    (net (code "48") (name "Net-(U2-STAT)") (class "Default")
      (node (ref "R24") (pin "1") (pinfunction "1_1") (pintype "passive"))
      (node (ref "U2") (pin "1") (pinfunction "STAT_1") (pintype "output"))
    )
    (net (code "49") (name "unconnected-(J1_RAIN-Pad1)") (class "Default")
      (node (ref "J1_RAIN") (pin "1") (pinfunction "1_1") (pintype "passive"))
    )
    (net (code "50") (name "unconnected-(J1_RAIN-Pad2)") (class "Default")
      (node (ref "J1_RAIN") (pin "2") (pinfunction "2_2") (pintype "passive"))
    )
    (net (code "51") (name "unconnected-(J1_RAIN-Pad5)") (class "Default")
      (node (ref "J1_RAIN") (pin "5") (pinfunction "5_5") (pintype "passive"))
    )
    (net (code "52") (name "unconnected-(J1_RAIN-Pad6)") (class "Default")
      (node (ref "J1_RAIN") (pin "6") (pinfunction "6_6") (pintype "passive"))
    )
    (net (code "53") (name "unconnected-(J2_WIND-Pad1)") (class "Default")
      (node (ref "J2_WIND") (pin "1") (pinfunction "1_1") (pintype "passive"))
    )
    (net (code "54") (name "unconnected-(J2_WIND-Pad6)") (class "Default")
      (node (ref "J2_WIND") (pin "6") (pinfunction "6_6") (pintype "passive"))
    )
    (net (code "55") (name "unconnected-(U$2-CLK-PadP$7)") (class "Default")
      (node (ref "U$2") (pin "P$7") (pinfunction "CLK_P$7") (pintype "bidirectional"))
    )
    (net (code "56") (name "unconnected-(U$2-MISO-PadP$9)") (class "Default")
      (node (ref "U$2") (pin "P$9") (pinfunction "MISO_P$9") (pintype "bidirectional"))
    )
    (net (code "57") (name "unconnected-(U$2-MOSI-PadP$8)") (class "Default")
      (node (ref "U$2") (pin "P$8") (pinfunction "MOSI_P$8") (pintype "bidirectional"))
    )
    (net (code "58") (name "unconnected-(U$2-P8-PadP$10)") (class "Default")
      (node (ref "U$2") (pin "P$10") (pinfunction "P8_P$10") (pintype "bidirectional"))
    )
    (net (code "59") (name "unconnected-(U$2-P12-PadP$14)") (class "Default")
      (node (ref "U$2") (pin "P$14") (pinfunction "P12_P$14") (pintype "bidirectional"))
    )
    (net (code "60") (name "unconnected-(U$2-P16-PadP$18)") (class "Default")
      (node (ref "U$2") (pin "P$18") (pinfunction "P16_P$18") (pintype "bidirectional"))
    )
    (net (code "61") (name "unconnected-(U$2-P18-PadP$20)") (class "Default")
      (node (ref "U$2") (pin "P$20") (pinfunction "P18_P$20") (pintype "bidirectional"))
    )
    (net (code "62") (name "unconnected-(U$2-P22-PadP$24)") (class "Default")
      (node (ref "U$2") (pin "P$24") (pinfunction "P22_P$24") (pintype "bidirectional"))
    )
  )
)
